# AC-PWR-v2_0.net
KiCad netlist of a schematic drawn in Altium Designer
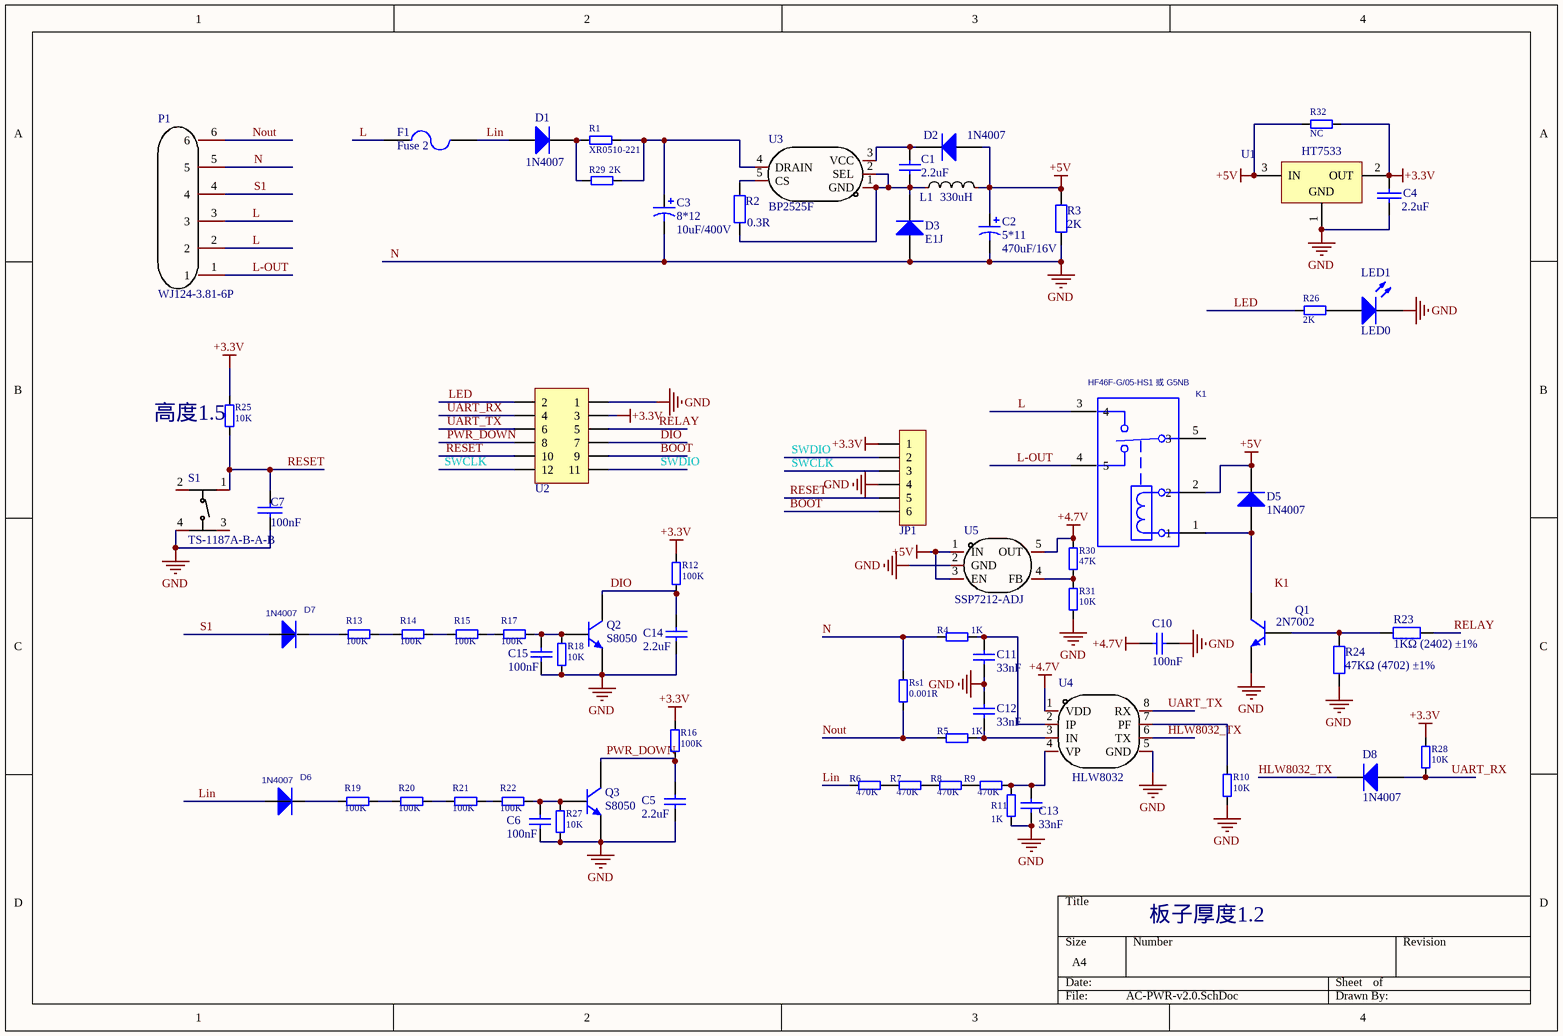
[diagram p0: AC-PWR-v2.0.SchDoc]

(export (version "E")
  (design (tool "Eeschema 10.0.6"))
  (components
    (comp (ref "C1")
      (value "2.2uF")
      (footprint "0805_C")
      (description "Capacitor")
      (fields (field (name "Comment") "1uF") (field (name "PUBLISHER") "Altium Limited"))
      (libsource (lib "Miscellaneous Devices") (part "Cap"))
    )
    (comp (ref "C2")
      (value "5*11")
      (footprint "CE/2 *5-11")
      (description "Polarized Capacitor (Surface Mount)")
      (fields (field (name "ALTIUM_VALUE") "470uF/16V") (field (name "PUBLISHER") "Altium Limited"))
      (libsource (lib "Miscellaneous Devices") (part "Cap Pol3"))
    )
    (comp (ref "C3")
      (value "8*12")
      (footprint "Cap8*12")
      (description "Polarized Capacitor (Surface Mount)")
      (fields (field (name "ALTIUM_VALUE") "10uF/400V") (field (name "PUBLISHER") "Altium Limited"))
      (libsource (lib "Miscellaneous Devices") (part "Cap Pol3"))
    )
    (comp (ref "C4")
      (value "2.2uF")
      (footprint "0603_C")
      (description "Capacitor")
      (libsource (lib "*") (part "CAP"))
    )
    (comp (ref "C5")
      (value "2.2uF")
      (footprint "0603_C")
      (description "Capacitor")
      (fields (field (name "Comment") "Cap") (field (name "PUBLISHER") "Altium Limited"))
      (libsource (lib "Miscellaneous Devices") (part "Cap"))
    )
    (comp (ref "C6")
      (value "100nF")
      (footprint "0603_C")
      (description "Capacitor")
      (fields (field (name "Comment") "Cap") (field (name "PUBLISHER") "Altium Limited"))
      (libsource (lib "Miscellaneous Devices") (part "Cap"))
    )
    (comp (ref "C7")
      (value "100nF")
      (footprint "0603_C")
      (description "Capacitor")
      (libsource (lib "") (part "CAP_1"))
    )
    (comp (ref "C10")
      (value "100nF")
      (footprint "0603_C")
      (description "Capacitor")
      (fields (field (name "Comment") "Cap") (field (name "PUBLISHER") "Altium Limited"))
      (libsource (lib "Miscellaneous Devices") (part "Cap"))
    )
    (comp (ref "C11")
      (value "33nF")
      (footprint "0603_C")
      (description "Capacitor")
      (fields (field (name "Comment") "Cap") (field (name "PUBLISHER") "Altium Limited"))
      (libsource (lib "Miscellaneous Devices") (part "Cap"))
    )
    (comp (ref "C12")
      (value "33nF")
      (footprint "0603_C")
      (description "Capacitor")
      (fields (field (name "Comment") "Cap") (field (name "PUBLISHER") "Altium Limited"))
      (libsource (lib "Miscellaneous Devices") (part "Cap"))
    )
    (comp (ref "C13")
      (value "33nF")
      (footprint "0805_C")
      (description "Capacitor")
      (fields (field (name "Comment") "Cap") (field (name "PUBLISHER") "Altium Limited"))
      (libsource (lib "Miscellaneous Devices") (part "Cap"))
    )
    (comp (ref "C14")
      (value "2.2uF")
      (footprint "0603_C")
      (description "Capacitor")
      (fields (field (name "Comment") "Cap") (field (name "PUBLISHER") "Altium Limited"))
      (libsource (lib "Miscellaneous Devices") (part "Cap"))
    )
    (comp (ref "C15")
      (value "100nF")
      (footprint "0603_C")
      (description "Capacitor")
      (fields (field (name "Comment") "Cap") (field (name "PUBLISHER") "Altium Limited"))
      (libsource (lib "Miscellaneous Devices") (part "Cap"))
    )
    (comp (ref "D1")
      (value "1N4007")
      (footprint "SOD-123")
      (description "开关二极管")
      (libsource (lib "Miscellaneous Devices LC") (part "LL-34 LL4148 LL-34 1206"))
    )
    (comp (ref "D2")
      (value "1N4007")
      (footprint "SOD-123")
      (description "开关二极管")
      (libsource (lib "Miscellaneous Devices LC") (part "LL-34 LL4148 LL-34 1206"))
    )
    (comp (ref "D3")
      (value "E1J")
      (footprint "SOD-123")
      (description "开关二极管")
      (libsource (lib "Miscellaneous Devices LC") (part "LL-34 LL4148 LL-34 1206"))
    )
    (comp (ref "D5")
      (value "1N4007")
      (footprint "SOD-123")
      (description "开关二极管")
      (libsource (lib "Miscellaneous Devices LC") (part "LL-34 LL4148 LL-34 1206"))
    )
    (comp (ref "D6")
      (value "D_M7")
      (footprint "SOD-123F")
      (fields (field (name "MODEL NUMBER") "1N4007"))
      (libsource (lib "*") (part "D"))
    )
    (comp (ref "D7")
      (value "D_M7")
      (footprint "SOD-123F")
      (fields (field (name "MODEL NUMBER") "1N4007"))
      (libsource (lib "*") (part "D"))
    )
    (comp (ref "D8")
      (value "1N4007")
      (footprint "SOD-123")
      (description "开关二极管")
      (libsource (lib "Miscellaneous Devices LC") (part "LL-34 LL4148 LL-34 1206"))
    )
    (comp (ref "F1")
      (value "Fuse 2")
      (footprint "PCBComponent_1 - duplicate1")
      (description "Fuse")
      (fields (field (name "PUBLISHER") "Altium Limited"))
      (libsource (lib "Miscellaneous Devices") (part "Fuse 2"))
    )
    (comp (ref "JP1")
      (value "HDR-1X6")
      (footprint "HDR2.0-LI-6P")
      (description "6P接插件")
      (libsource (lib "5.4 - 2.0mm连接器(排针排母)") (part "Header 6"))
    )
    (comp (ref "K1")
      (value "HF46F-G/05-HS1 或 G5NB")
      (footprint "HF46F-F")
      (description "1A SPDT RELAY 16 X 12 DUAL INLINE PITCH")
      (libsource (lib "*") (part "RLY-MZ-SPDT"))
    )
    (comp (ref "L1")
      (value "330uH")
      (footprint "L3.5-8X11.5")
      (description "SLP0810R-331KTT")
      (fields
        (field (name "NAME") "330uH")
        (field (name "MANUFACTURER") "cjiang(长江微电)")
        (field (name "MANUFACTURER PART") "FNR5040S3R0NT")
      )
      (libsource (lib "altium-import") (part "root_0_FNR5040S3R0NT_"))
    )
    (comp (ref "LED1")
      (value "LED0")
      (footprint "0603_LED_S1")
      (description "Typical INFRARED GaAs LED")
      (fields (field (name "PUBLISHER") "Altium Limited"))
      (libsource (lib "Miscellaneous Devices") (part "LED0"))
    )
    (comp (ref "P1")
      (value "WJ124-3.81-6P")
      (footprint "CONN-TH_6P-P5.00_WJ500V-5.08-3P")
      (fields (field (name "NAME") "WJ124-3.81-6P") (field (name "MANUFACTURER") "KANGNEX(康奈克斯电气)"))
      (libsource (lib "altium-import") (part "root_2_mirrored_WJ124-3.81-6P_"))
    )
    (comp (ref "Q1")
      (value "2N7002")
      (footprint "SOT-23(SOT-23-3)")
      (description "三极管")
      (libsource (lib "Miscellaneous Devices LC") (part "SOT-23 MMBT5551  G1"))
    )
    (comp (ref "Q2")
      (value "S8050")
      (footprint "SOT-23-3L")
      (description "NPN General Purpose Amplifier")
      (fields (field (name "PUBLISHER") "Altium Limited"))
      (libsource (lib "Miscellaneous Devices") (part "2N3904"))
    )
    (comp (ref "Q3")
      (value "S8050")
      (footprint "SOT-23-3L")
      (description "NPN General Purpose Amplifier")
      (fields (field (name "PUBLISHER") "Altium Limited"))
      (libsource (lib "Miscellaneous Devices") (part "2N3904"))
    )
    (comp (ref "R1")
      (value "XR0510-221")
      (footprint "PCBComponent_1 - duplicate")
      (description "KNP2WS-33R")
      (libsource (lib "") (part "RES2_1"))
    )
    (comp (ref "R2")
      (value "0.3R")
      (footprint "1206_R")
      (description "贴片电阻")
      (libsource (lib "Miscellaneous Devices LC") (part "0603 24KΩ (2402) 1%"))
    )
    (comp (ref "R3")
      (value "2K")
      (footprint "0603_R")
      (description "贴片电阻")
      (libsource (lib "") (part "0603 24KΩ (2402) 1%_2"))
    )
    (comp (ref "R4")
      (value "1K")
      (footprint "0603_R")
      (description "resistor")
      (libsource (lib "*") (part "RES2"))
    )
    (comp (ref "R5")
      (value "1K")
      (footprint "0603_R")
      (description "resistor")
      (libsource (lib "*") (part "RES2"))
    )
    (comp (ref "R6")
      (value "470K")
      (footprint "0805_R")
      (description "resistor")
      (libsource (lib "*") (part "RES2"))
    )
    (comp (ref "R7")
      (value "470K")
      (footprint "0805_R")
      (description "resistor")
      (libsource (lib "*") (part "RES2"))
    )
    (comp (ref "R8")
      (value "470K")
      (footprint "0805_R")
      (description "resistor")
      (libsource (lib "*") (part "RES2"))
    )
    (comp (ref "R9")
      (value "470K")
      (footprint "0805_R")
      (description "resistor")
      (libsource (lib "*") (part "RES2"))
    )
    (comp (ref "R10")
      (value "10K")
      (footprint "0603_R")
      (description "resistor")
      (libsource (lib "*") (part "RES2"))
    )
    (comp (ref "R11")
      (value "1K")
      (footprint "0805_R")
      (description "resistor")
      (libsource (lib "*") (part "RES2"))
    )
    (comp (ref "R12")
      (value "100K")
      (footprint "0603_R")
      (description "resistor")
      (libsource (lib "*") (part "RES2"))
    )
    (comp (ref "R13")
      (value "100K")
      (footprint "0805_R")
      (description "resistor")
      (libsource (lib "*") (part "RES2"))
    )
    (comp (ref "R14")
      (value "100K")
      (footprint "0805_R")
      (description "resistor")
      (libsource (lib "*") (part "RES2"))
    )
    (comp (ref "R15")
      (value "100K")
      (footprint "0805_R")
      (description "resistor")
      (libsource (lib "*") (part "RES2"))
    )
    (comp (ref "R16")
      (value "100K")
      (footprint "0603_R")
      (description "resistor")
      (libsource (lib "*") (part "RES2"))
    )
    (comp (ref "R17")
      (value "100K")
      (footprint "0805_R")
      (description "resistor")
      (libsource (lib "*") (part "RES2"))
    )
    (comp (ref "R18")
      (value "10K")
      (footprint "0603_R")
      (description "resistor")
      (libsource (lib "*") (part "RES2"))
    )
    (comp (ref "R19")
      (value "100K")
      (footprint "0805_R")
      (description "resistor")
      (libsource (lib "*") (part "RES2"))
    )
    (comp (ref "R20")
      (value "100K")
      (footprint "0805_R")
      (description "resistor")
      (libsource (lib "*") (part "RES2"))
    )
    (comp (ref "R21")
      (value "100K")
      (footprint "0805_R")
      (description "resistor")
      (libsource (lib "*") (part "RES2"))
    )
    (comp (ref "R22")
      (value "100K")
      (footprint "0805_R")
      (description "resistor")
      (libsource (lib "*") (part "RES2"))
    )
    (comp (ref "R23")
      (value "1KΩ (2402) ±1%")
      (footprint "0603_R")
      (description "贴片电阻")
      (libsource (lib "") (part "0603 24KΩ (2402) 1%_1"))
    )
    (comp (ref "R24")
      (value "47KΩ (4702) ±1%")
      (footprint "0603_R")
      (description "贴片电阻")
      (libsource (lib "Miscellaneous Devices LC") (part "0603 47KΩ (4702) 1%"))
    )
    (comp (ref "R25")
      (value "10K")
      (footprint "0603_R")
      (description "resistor")
      (libsource (lib "") (part "RES2_1"))
    )
    (comp (ref "R26")
      (value "2K")
      (footprint "0603_R")
      (description "resistor")
      (libsource (lib "") (part "RES2_1"))
    )
    (comp (ref "R27")
      (value "10K")
      (footprint "0603_R")
      (description "resistor")
      (libsource (lib "*") (part "RES2"))
    )
    (comp (ref "R28")
      (value "10K")
      (footprint "0603_R")
      (description "resistor")
      (libsource (lib "*") (part "RES2"))
    )
    (comp (ref "R29")
      (value "2K")
      (footprint "2010_R")
      (description "resistor")
      (libsource (lib "*") (part "RES2"))
    )
    (comp (ref "R30")
      (value "47K")
      (footprint "0603_R")
      (description "resistor")
      (libsource (lib "*") (part "RES2"))
    )
    (comp (ref "R31")
      (value "10K")
      (footprint "0603_R")
      (description "resistor")
      (libsource (lib "*") (part "RES2"))
    )
    (comp (ref "R32")
      (value "NC")
      (footprint "0603_R")
      (description "resistor")
      (libsource (lib "") (part "RES2_1"))
    )
    (comp (ref "Rs1")
      (value "0.001R")
      (footprint "2512_R")
      (description "resistor")
      (libsource (lib "*") (part "RES2"))
    )
    (comp (ref "S1")
      (value "TS-1187A-B-A-B")
      (footprint "SW-SMD_4P-L5.1-W5.1-P3.70-LS6.5-TL-2")
      (description "触点电流:50mA;额定电压(DC):12V;绝缘电阻:-;电路结构:单刀单掷;安装方式:立贴;带灯:无;作用力:160gf;机械寿命:10万次;带支架:否;")
      (fields (field (name "NAME") "TS-1187A-B-A-B") (field (name "MANUFACTURER") "XKB Connectivity(中国星坤)"))
      (libsource (lib "altium-import") (part "root_0_mirrored_TS-1187A-B-A-B_"))
    )
    (comp (ref "U1")
      (value "HT7533")
      (footprint "SOT-23(SOT-23-3)")
      (description "1.5A Low Dropout Positive Regulators")
      (fields
        (field (name "PARTNUMBER") "LM1086IT-3.3")
        (field (name "MANUFACTURER") "National Semiconductor")
        (field (name "PUBLISHER") "Altium Limited")
      )
      (libsource (lib "NSC LDO") (part "LM1086IT-3.3"))
    )
    (comp (ref "U2")
      (value "Header 6X2")
      (footprint "module")
      (description "6*2P接插件")
      (libsource (lib "5.4 - 2.0mm连接器(排针排母)") (part "Header  6X2"))
    )
    (comp (ref "U3")
      (value "BP2525F")
      (footprint "SOT33-5A_L3.9-W2.6-P0.90-BP2525D")
      (description "功能类型:降压型;输出电压:5V；3.3V;输出电流(最大值):500mA;")
      (fields (field (name "NAME") "BP2525F") (field (name "MANUFACTURER") "BPS(上海晶丰明源)"))
      (libsource (lib "altium-import") (part "root_2_BP2525F_"))
    )
    (comp (ref "U4")
      (value "HLW8032")
      (footprint "SOP-8_150mil")
      (description "HLW8012的升级版串口输出所有数据")
      (fields (field (name "NAME") "HLW8032") (field (name "MANUFACTURER") "合力为"))
      (libsource (lib "altium-import") (part "root_0_HLW8032_"))
    )
    (comp (ref "U5")
      (value "ZTP7001-00")
      (footprint "SOT-23-5")
      (description "输出类型:可调;最大输入电压:6V;最大输出电流:600mA;电源纹波抑制比(PSRR):70dB@(1kHz);输出极性:正极;")
      (fields (field (name "NAME") "SSP7212-ADJ") (field (name "MANUFACTURER") "ZILLTEK(钰太)"))
      (libsource (lib "altium-import") (part "root_0_ZTP7001-00_"))
    )
  )
  (nets
    (net (code "1") (name "+3.3V") (class "Default")
      (node (ref "C4") (pin "1") (pinfunction "1_1") (pintype "passive"))
      (node (ref "JP1") (pin "1") (pinfunction "1_1") (pintype "passive"))
      (node (ref "R12") (pin "2") (pinfunction "2_2") (pintype "passive"))
      (node (ref "R16") (pin "2") (pinfunction "2_2") (pintype "passive"))
      (node (ref "R25") (pin "2") (pinfunction "2_2") (pintype "passive"))
      (node (ref "R28") (pin "1") (pinfunction "1_1") (pintype "passive"))
      (node (ref "R32") (pin "1") (pinfunction "1_1") (pintype "passive"))
      (node (ref "U1") (pin "2") (pinfunction "OUT_2") (pintype "power_in"))
      (node (ref "U2") (pin "3") (pinfunction "3_3") (pintype "passive"))
    )
    (net (code "2") (name "+4.7V") (class "Default")
      (node (ref "C10") (pin "1") (pinfunction "1_1") (pintype "passive"))
      (node (ref "R30") (pin "1") (pinfunction "1_1") (pintype "passive"))
      (node (ref "U4") (pin "1") (pinfunction "VDD_1") (pintype "passive"))
      (node (ref "U5") (pin "5") (pinfunction "OUT_5") (pintype "passive"))
    )
    (net (code "3") (name "+5V") (class "Default")
      (node (ref "C2") (pin "1") (pinfunction "1_1") (pintype "passive"))
      (node (ref "D2") (pin "1") (pinfunction "A_1") (pintype "passive"))
      (node (ref "D5") (pin "2") (pinfunction "K_2") (pintype "passive"))
      (node (ref "K1") (pin "2") (pinfunction "2_2") (pintype "passive"))
      (node (ref "L1") (pin "2") (pinfunction "2_2") (pintype "passive"))
      (node (ref "R3") (pin "1") (pinfunction "1_1") (pintype "passive"))
      (node (ref "R32") (pin "2") (pinfunction "2_2") (pintype "passive"))
      (node (ref "U1") (pin "3") (pinfunction "IN_3") (pintype "power_in"))
      (node (ref "U5") (pin "1") (pinfunction "IN_1") (pintype "passive"))
      (node (ref "U5") (pin "3") (pinfunction "EN_3") (pintype "passive"))
    )
    (net (code "4") (name "/BOOT") (class "Default")
      (node (ref "JP1") (pin "6") (pinfunction "6_6") (pintype "passive"))
      (node (ref "U2") (pin "9") (pinfunction "9_9") (pintype "passive"))
    )
    (net (code "5") (name "/DIO") (class "Default")
      (node (ref "C14") (pin "2") (pinfunction "2_2") (pintype "passive"))
      (node (ref "Q2") (pin "3") (pinfunction "C_3") (pintype "passive"))
      (node (ref "R12") (pin "1") (pinfunction "1_1") (pintype "passive"))
      (node (ref "U2") (pin "7") (pinfunction "7_7") (pintype "passive"))
    )
    (net (code "6") (name "/HLW8032_TX") (class "Default")
      (node (ref "D8") (pin "2") (pinfunction "K_2") (pintype "passive"))
      (node (ref "U4") (pin "6") (pinfunction "TX_6") (pintype "passive"))
    )
    (net (code "8") (name "/L") (class "Default")
      (node (ref "F1") (pin "1") (pinfunction "1_1") (pintype "passive"))
      (node (ref "K1") (pin "3") (pinfunction "4_3") (pintype "passive"))
      (node (ref "P1") (pin "2") (pinfunction "2_2") (pintype "passive"))
      (node (ref "P1") (pin "3") (pinfunction "3_3") (pintype "passive"))
    )
    (net (code "9") (name "/L-OUT") (class "Default")
      (node (ref "K1") (pin "4") (pinfunction "5_4") (pintype "passive"))
      (node (ref "P1") (pin "1") (pinfunction "1_1") (pintype "passive"))
    )
    (net (code "10") (name "/LED") (class "Default")
      (node (ref "R26") (pin "2") (pinfunction "2_2") (pintype "passive"))
      (node (ref "U2") (pin "2") (pinfunction "2_2") (pintype "passive"))
    )
    (net (code "11") (name "/Lin") (class "Default")
      (node (ref "D1") (pin "1") (pinfunction "A_1") (pintype "passive"))
      (node (ref "D6") (pin "1") (pinfunction "1_1") (pintype "passive"))
      (node (ref "F1") (pin "2") (pinfunction "2_2") (pintype "passive"))
      (node (ref "R6") (pin "1") (pinfunction "1_1") (pintype "passive"))
    )
    (net (code "12") (name "/Nout") (class "Default")
      (node (ref "P1") (pin "6") (pinfunction "6_6") (pintype "passive"))
      (node (ref "R5") (pin "2") (pinfunction "2_2") (pintype "passive"))
      (node (ref "Rs1") (pin "2") (pinfunction "2_2") (pintype "passive"))
    )
    (net (code "13") (name "/PWR_DOWN") (class "Default")
      (node (ref "C5") (pin "2") (pinfunction "2_2") (pintype "passive"))
      (node (ref "Q3") (pin "3") (pinfunction "C_3") (pintype "passive"))
      (node (ref "R16") (pin "1") (pinfunction "1_1") (pintype "passive"))
      (node (ref "U2") (pin "8") (pinfunction "8_8") (pintype "passive"))
    )
    (net (code "14") (name "/RELAY") (class "Default")
      (node (ref "R23") (pin "1") (pinfunction "1_1") (pintype "passive"))
      (node (ref "U2") (pin "5") (pinfunction "5_5") (pintype "passive"))
    )
    (net (code "15") (name "/RESET") (class "Default")
      (node (ref "C7") (pin "2") (pinfunction "2_2") (pintype "passive"))
      (node (ref "JP1") (pin "5") (pinfunction "5_5") (pintype "passive"))
      (node (ref "R25") (pin "1") (pinfunction "1_1") (pintype "passive"))
      (node (ref "S1") (pin "1") (pinfunction "A_1") (pintype "passive"))
      (node (ref "U2") (pin "10") (pinfunction "10_10") (pintype "passive"))
    )
    (net (code "16") (name "/S1") (class "Default")
      (node (ref "D7") (pin "1") (pinfunction "1_1") (pintype "passive"))
      (node (ref "P1") (pin "4") (pinfunction "4_4") (pintype "passive"))
    )
    (net (code "17") (name "/SWCLK") (class "Default")
      (node (ref "JP1") (pin "3") (pinfunction "3_3") (pintype "passive"))
      (node (ref "U2") (pin "12") (pinfunction "12_12") (pintype "passive"))
    )
    (net (code "18") (name "/SWDIO") (class "Default")
      (node (ref "JP1") (pin "2") (pinfunction "2_2") (pintype "passive"))
      (node (ref "U2") (pin "11") (pinfunction "11_11") (pintype "passive"))
    )
    (net (code "19") (name "/UART_RX") (class "Default")
      (node (ref "D8") (pin "1") (pinfunction "A_1") (pintype "passive"))
      (node (ref "R28") (pin "2") (pinfunction "2_2") (pintype "passive"))
      (node (ref "U2") (pin "4") (pinfunction "4_4") (pintype "passive"))
    )
    (net (code "20") (name "/UART_TX") (class "Default")
      (node (ref "U2") (pin "6") (pinfunction "6_6") (pintype "passive"))
      (node (ref "U4") (pin "8") (pinfunction "RX_8") (pintype "passive"))
    )
    (net (code "21") (name "GND") (class "Default")
      (node (ref "C10") (pin "2") (pinfunction "2_2") (pintype "passive"))
      (node (ref "C11") (pin "1") (pinfunction "1_1") (pintype "passive"))
      (node (ref "C12") (pin "2") (pinfunction "2_2") (pintype "passive"))
      (node (ref "C13") (pin "1") (pinfunction "1_1") (pintype "passive"))
      (node (ref "C14") (pin "1") (pinfunction "1_1") (pintype "passive"))
      (node (ref "C15") (pin "1") (pinfunction "1_1") (pintype "passive"))
      (node (ref "C2") (pin "2") (pinfunction "2_2") (pintype "passive"))
      (node (ref "C3") (pin "2") (pinfunction "2_2") (pintype "passive"))
      (node (ref "C4") (pin "2") (pinfunction "2_2") (pintype "passive"))
      (node (ref "C5") (pin "1") (pinfunction "1_1") (pintype "passive"))
      (node (ref "C6") (pin "1") (pinfunction "1_1") (pintype "passive"))
      (node (ref "C7") (pin "1") (pinfunction "1_1") (pintype "passive"))
      (node (ref "D3") (pin "1") (pinfunction "A_1") (pintype "passive"))
      (node (ref "JP1") (pin "4") (pinfunction "4_4") (pintype "passive"))
      (node (ref "LED1") (pin "K") (pinfunction "K_K") (pintype "passive"))
      (node (ref "P1") (pin "5") (pinfunction "5_5") (pintype "passive"))
      (node (ref "Q1") (pin "2") (pinfunction "E_2") (pintype "passive"))
      (node (ref "Q2") (pin "2") (pinfunction "E_2") (pintype "passive"))
      (node (ref "Q3") (pin "2") (pinfunction "E_2") (pintype "passive"))
      (node (ref "R10") (pin "2") (pinfunction "2_2") (pintype "passive"))
      (node (ref "R11") (pin "1") (pinfunction "1_1") (pintype "passive"))
      (node (ref "R18") (pin "1") (pinfunction "1_1") (pintype "passive"))
      (node (ref "R24") (pin "1") (pinfunction "1_1") (pintype "passive"))
      (node (ref "R27") (pin "1") (pinfunction "1_1") (pintype "passive"))
      (node (ref "R3") (pin "2") (pinfunction "2_2") (pintype "passive"))
      (node (ref "R31") (pin "2") (pinfunction "2_2") (pintype "passive"))
      (node (ref "R4") (pin "2") (pinfunction "2_2") (pintype "passive"))
      (node (ref "Rs1") (pin "1") (pinfunction "1_1") (pintype "passive"))
      (node (ref "S1") (pin "4") (pinfunction "D_4") (pintype "passive"))
      (node (ref "U1") (pin "1") (pinfunction "GND_1") (pintype "power_in"))
      (node (ref "U2") (pin "1") (pinfunction "1_1") (pintype "passive"))
      (node (ref "U4") (pin "5") (pinfunction "GND_5") (pintype "passive"))
      (node (ref "U5") (pin "2") (pinfunction "GND_2") (pintype "passive"))
    )
    (net (code "22") (name "Net-(D1-K)") (class "Default")
      (node (ref "D1") (pin "2") (pinfunction "K_2") (pintype "passive"))
      (node (ref "R1") (pin "1") (pinfunction "1_1") (pintype "passive"))
      (node (ref "R29") (pin "2") (pinfunction "2_2") (pintype "passive"))
    )
    (net (code "23") (name "Net-(D2-K)") (class "Default")
      (node (ref "C1") (pin "2") (pinfunction "2_2") (pintype "passive"))
      (node (ref "D2") (pin "2") (pinfunction "K_2") (pintype "passive"))
      (node (ref "U3") (pin "3") (pinfunction "VCC_3") (pintype "passive"))
    )
    (net (code "24") (name "Net-(D3-K)") (class "Default")
      (node (ref "C1") (pin "1") (pinfunction "1_1") (pintype "passive"))
      (node (ref "D3") (pin "2") (pinfunction "K_2") (pintype "passive"))
      (node (ref "L1") (pin "1") (pinfunction "1_1") (pintype "passive"))
      (node (ref "R2") (pin "1") (pinfunction "1_1") (pintype "passive"))
      (node (ref "U3") (pin "1") (pinfunction "GND_1") (pintype "passive"))
      (node (ref "U3") (pin "2") (pinfunction "SEL_2") (pintype "passive"))
    )
    (net (code "25") (name "Net-(D5-A)") (class "Default")
      (node (ref "D5") (pin "1") (pinfunction "A_1") (pintype "passive"))
      (node (ref "K1") (pin "1") (pinfunction "1_1") (pintype "passive"))
      (node (ref "Q1") (pin "3") (pinfunction "C_3") (pintype "passive"))
    )
    (net (code "26") (name "Net-(D6-Pad2)") (class "Default")
      (node (ref "D6") (pin "2") (pinfunction "2_2") (pintype "passive"))
      (node (ref "R19") (pin "1") (pinfunction "1_1") (pintype "passive"))
    )
    (net (code "27") (name "Net-(D7-Pad2)") (class "Default")
      (node (ref "D7") (pin "2") (pinfunction "2_2") (pintype "passive"))
      (node (ref "R13") (pin "1") (pinfunction "1_1") (pintype "passive"))
    )
    (net (code "28") (name "Net-(LED1-PadA)") (class "Default")
      (node (ref "LED1") (pin "A") (pinfunction "A_A") (pintype "passive"))
      (node (ref "R26") (pin "1") (pinfunction "1_1") (pintype "passive"))
    )
    (net (code "29") (name "Net-(Q1-B)") (class "Default")
      (node (ref "Q1") (pin "1") (pinfunction "B_1") (pintype "passive"))
      (node (ref "R23") (pin "2") (pinfunction "2_2") (pintype "passive"))
      (node (ref "R24") (pin "2") (pinfunction "2_2") (pintype "passive"))
    )
    (net (code "30") (name "Net-(Q2-B)") (class "Default")
      (node (ref "C15") (pin "2") (pinfunction "2_2") (pintype "passive"))
      (node (ref "Q2") (pin "1") (pinfunction "B_1") (pintype "passive"))
      (node (ref "R17") (pin "2") (pinfunction "2_2") (pintype "passive"))
      (node (ref "R18") (pin "2") (pinfunction "2_2") (pintype "passive"))
    )
    (net (code "31") (name "Net-(Q3-B)") (class "Default")
      (node (ref "C6") (pin "2") (pinfunction "2_2") (pintype "passive"))
      (node (ref "Q3") (pin "1") (pinfunction "B_1") (pintype "passive"))
      (node (ref "R22") (pin "2") (pinfunction "2_2") (pintype "passive"))
      (node (ref "R27") (pin "2") (pinfunction "2_2") (pintype "passive"))
    )
    (net (code "32") (name "Net-(R6-Pad2)") (class "Default")
      (node (ref "R6") (pin "2") (pinfunction "2_2") (pintype "passive"))
      (node (ref "R7") (pin "1") (pinfunction "1_1") (pintype "passive"))
    )
    (net (code "33") (name "Net-(R7-Pad2)") (class "Default")
      (node (ref "R7") (pin "2") (pinfunction "2_2") (pintype "passive"))
      (node (ref "R8") (pin "1") (pinfunction "1_1") (pintype "passive"))
    )
    (net (code "34") (name "Net-(R8-Pad2)") (class "Default")
      (node (ref "R8") (pin "2") (pinfunction "2_2") (pintype "passive"))
      (node (ref "R9") (pin "1") (pinfunction "1_1") (pintype "passive"))
    )
    (net (code "35") (name "Net-(R13-Pad2)") (class "Default")
      (node (ref "R13") (pin "2") (pinfunction "2_2") (pintype "passive"))
      (node (ref "R14") (pin "1") (pinfunction "1_1") (pintype "passive"))
    )
    (net (code "36") (name "Net-(R14-Pad2)") (class "Default")
      (node (ref "R14") (pin "2") (pinfunction "2_2") (pintype "passive"))
      (node (ref "R15") (pin "1") (pinfunction "1_1") (pintype "passive"))
    )
    (net (code "37") (name "Net-(R15-Pad2)") (class "Default")
      (node (ref "R15") (pin "2") (pinfunction "2_2") (pintype "passive"))
      (node (ref "R17") (pin "1") (pinfunction "1_1") (pintype "passive"))
    )
    (net (code "38") (name "Net-(R19-Pad2)") (class "Default")
      (node (ref "R19") (pin "2") (pinfunction "2_2") (pintype "passive"))
      (node (ref "R20") (pin "1") (pinfunction "1_1") (pintype "passive"))
    )
    (net (code "39") (name "Net-(R20-Pad2)") (class "Default")
      (node (ref "R20") (pin "2") (pinfunction "2_2") (pintype "passive"))
      (node (ref "R21") (pin "1") (pinfunction "1_1") (pintype "passive"))
    )
    (net (code "40") (name "Net-(R21-Pad2)") (class "Default")
      (node (ref "R21") (pin "2") (pinfunction "2_2") (pintype "passive"))
      (node (ref "R22") (pin "1") (pinfunction "1_1") (pintype "passive"))
    )
    (net (code "41") (name "Net-(U3-CS)") (class "Default")
      (node (ref "R2") (pin "2") (pinfunction "2_2") (pintype "passive"))
      (node (ref "U3") (pin "5") (pinfunction "CS_5") (pintype "passive"))
    )
    (net (code "42") (name "Net-(U3-DRAIN)") (class "Default")
      (node (ref "C3") (pin "1") (pinfunction "1_1") (pintype "passive"))
      (node (ref "R1") (pin "2") (pinfunction "2_2") (pintype "passive"))
      (node (ref "R29") (pin "1") (pinfunction "1_1") (pintype "passive"))
      (node (ref "U3") (pin "4") (pinfunction "DRAIN_4") (pintype "passive"))
    )
    (net (code "43") (name "Net-(U4-IN)") (class "Default")
      (node (ref "C12") (pin "1") (pinfunction "1_1") (pintype "passive"))
      (node (ref "R5") (pin "1") (pinfunction "1_1") (pintype "passive"))
      (node (ref "U4") (pin "3") (pinfunction "IN_3") (pintype "passive"))
    )
    (net (code "44") (name "Net-(U4-IP)") (class "Default")
      (node (ref "C11") (pin "2") (pinfunction "2_2") (pintype "passive"))
      (node (ref "R4") (pin "1") (pinfunction "1_1") (pintype "passive"))
      (node (ref "U4") (pin "2") (pinfunction "IP_2") (pintype "passive"))
    )
    (net (code "45") (name "Net-(U4-PF)") (class "Default")
      (node (ref "R10") (pin "1") (pinfunction "1_1") (pintype "passive"))
      (node (ref "U4") (pin "7") (pinfunction "PF_7") (pintype "passive"))
    )
    (net (code "46") (name "Net-(U4-VP)") (class "Default")
      (node (ref "C13") (pin "2") (pinfunction "2_2") (pintype "passive"))
      (node (ref "R11") (pin "2") (pinfunction "2_2") (pintype "passive"))
      (node (ref "R9") (pin "2") (pinfunction "2_2") (pintype "passive"))
      (node (ref "U4") (pin "4") (pinfunction "VP_4") (pintype "passive"))
    )
    (net (code "47") (name "Net-(U5-FB)") (class "Default")
      (node (ref "R30") (pin "2") (pinfunction "2_2") (pintype "passive"))
      (node (ref "R31") (pin "1") (pinfunction "1_1") (pintype "passive"))
      (node (ref "U5") (pin "4") (pinfunction "FB_4") (pintype "passive"))
    )
    (net (code "48") (name "unconnected-(K1-3-Pad5)") (class "Default")
      (node (ref "K1") (pin "5") (pinfunction "3_5") (pintype "passive"))
    )
    (net (code "49") (name "unconnected-(S1-B-Pad2)") (class "Default")
      (node (ref "S1") (pin "2") (pinfunction "B_2") (pintype "passive"))
    )
    (net (code "50") (name "unconnected-(S1-C-Pad3)") (class "Default")
      (node (ref "S1") (pin "3") (pinfunction "C_3") (pintype "passive"))
    )
  )
)
